# 1_Schematic_Antenna_Mini-Whip_SMD.net
KiCad netlist of a schematic drawn in EasyEDA
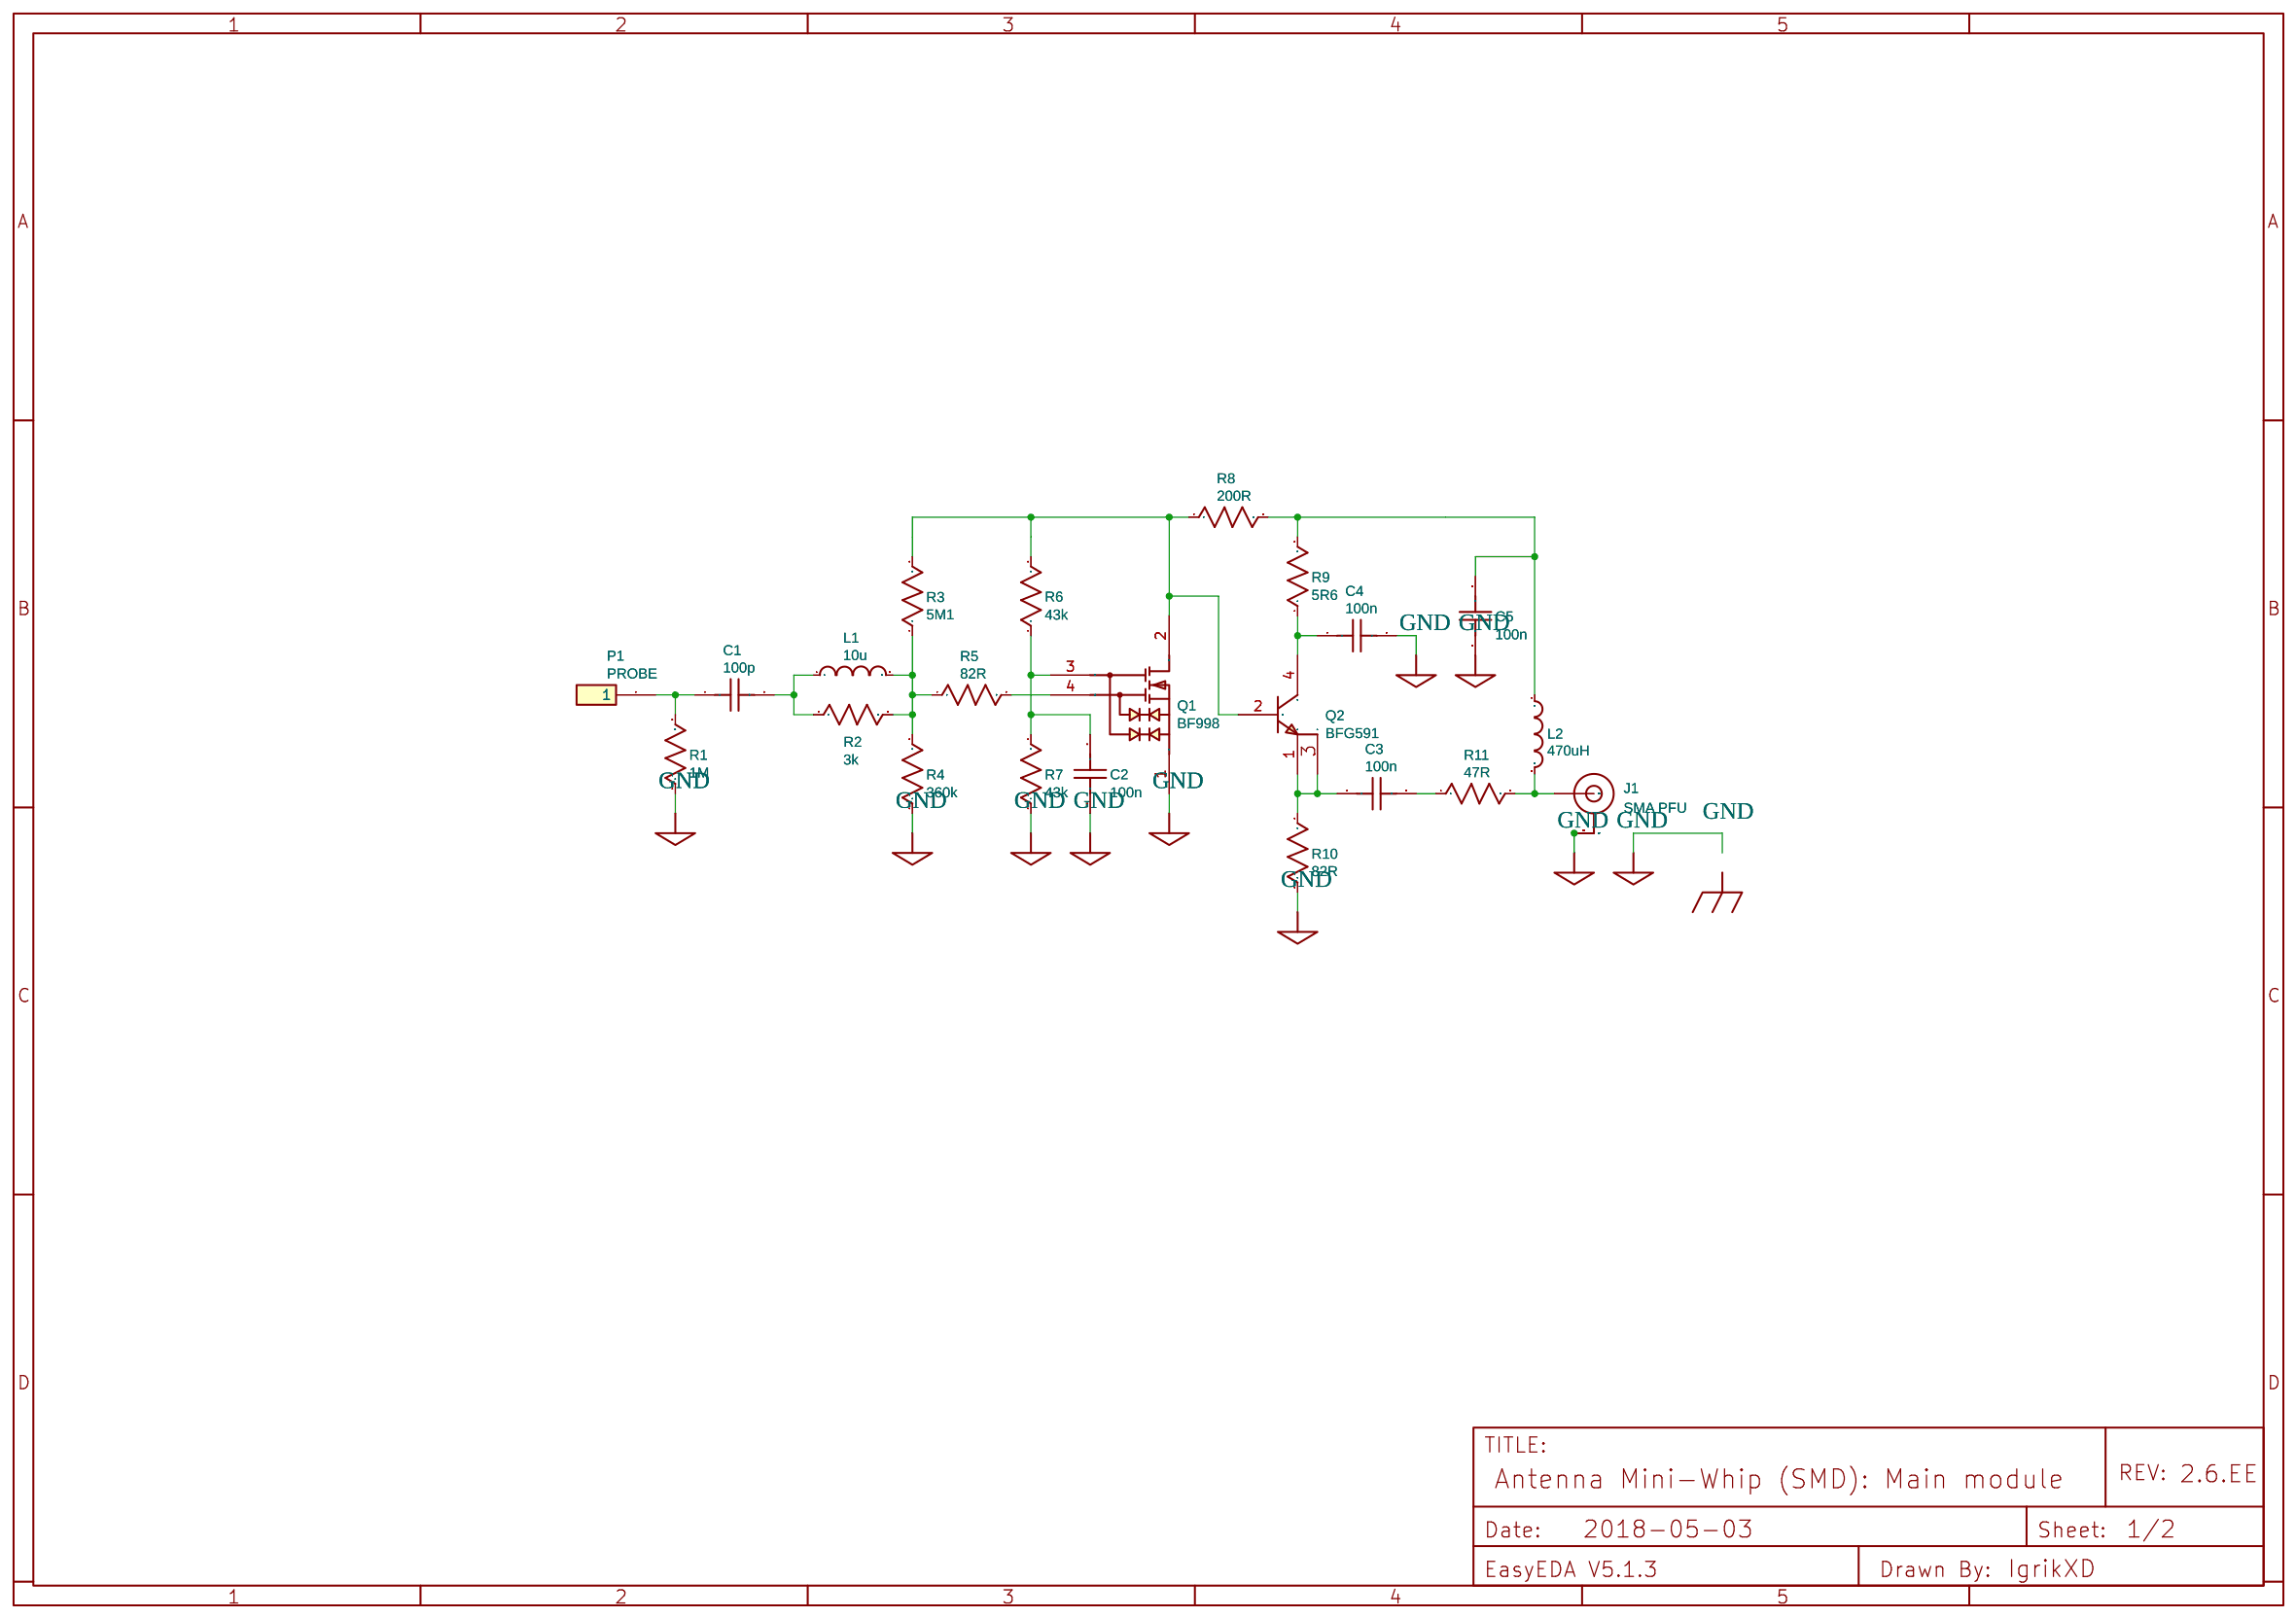
[diagram p0: Antenna Mini-Whip (SMD): Main module]
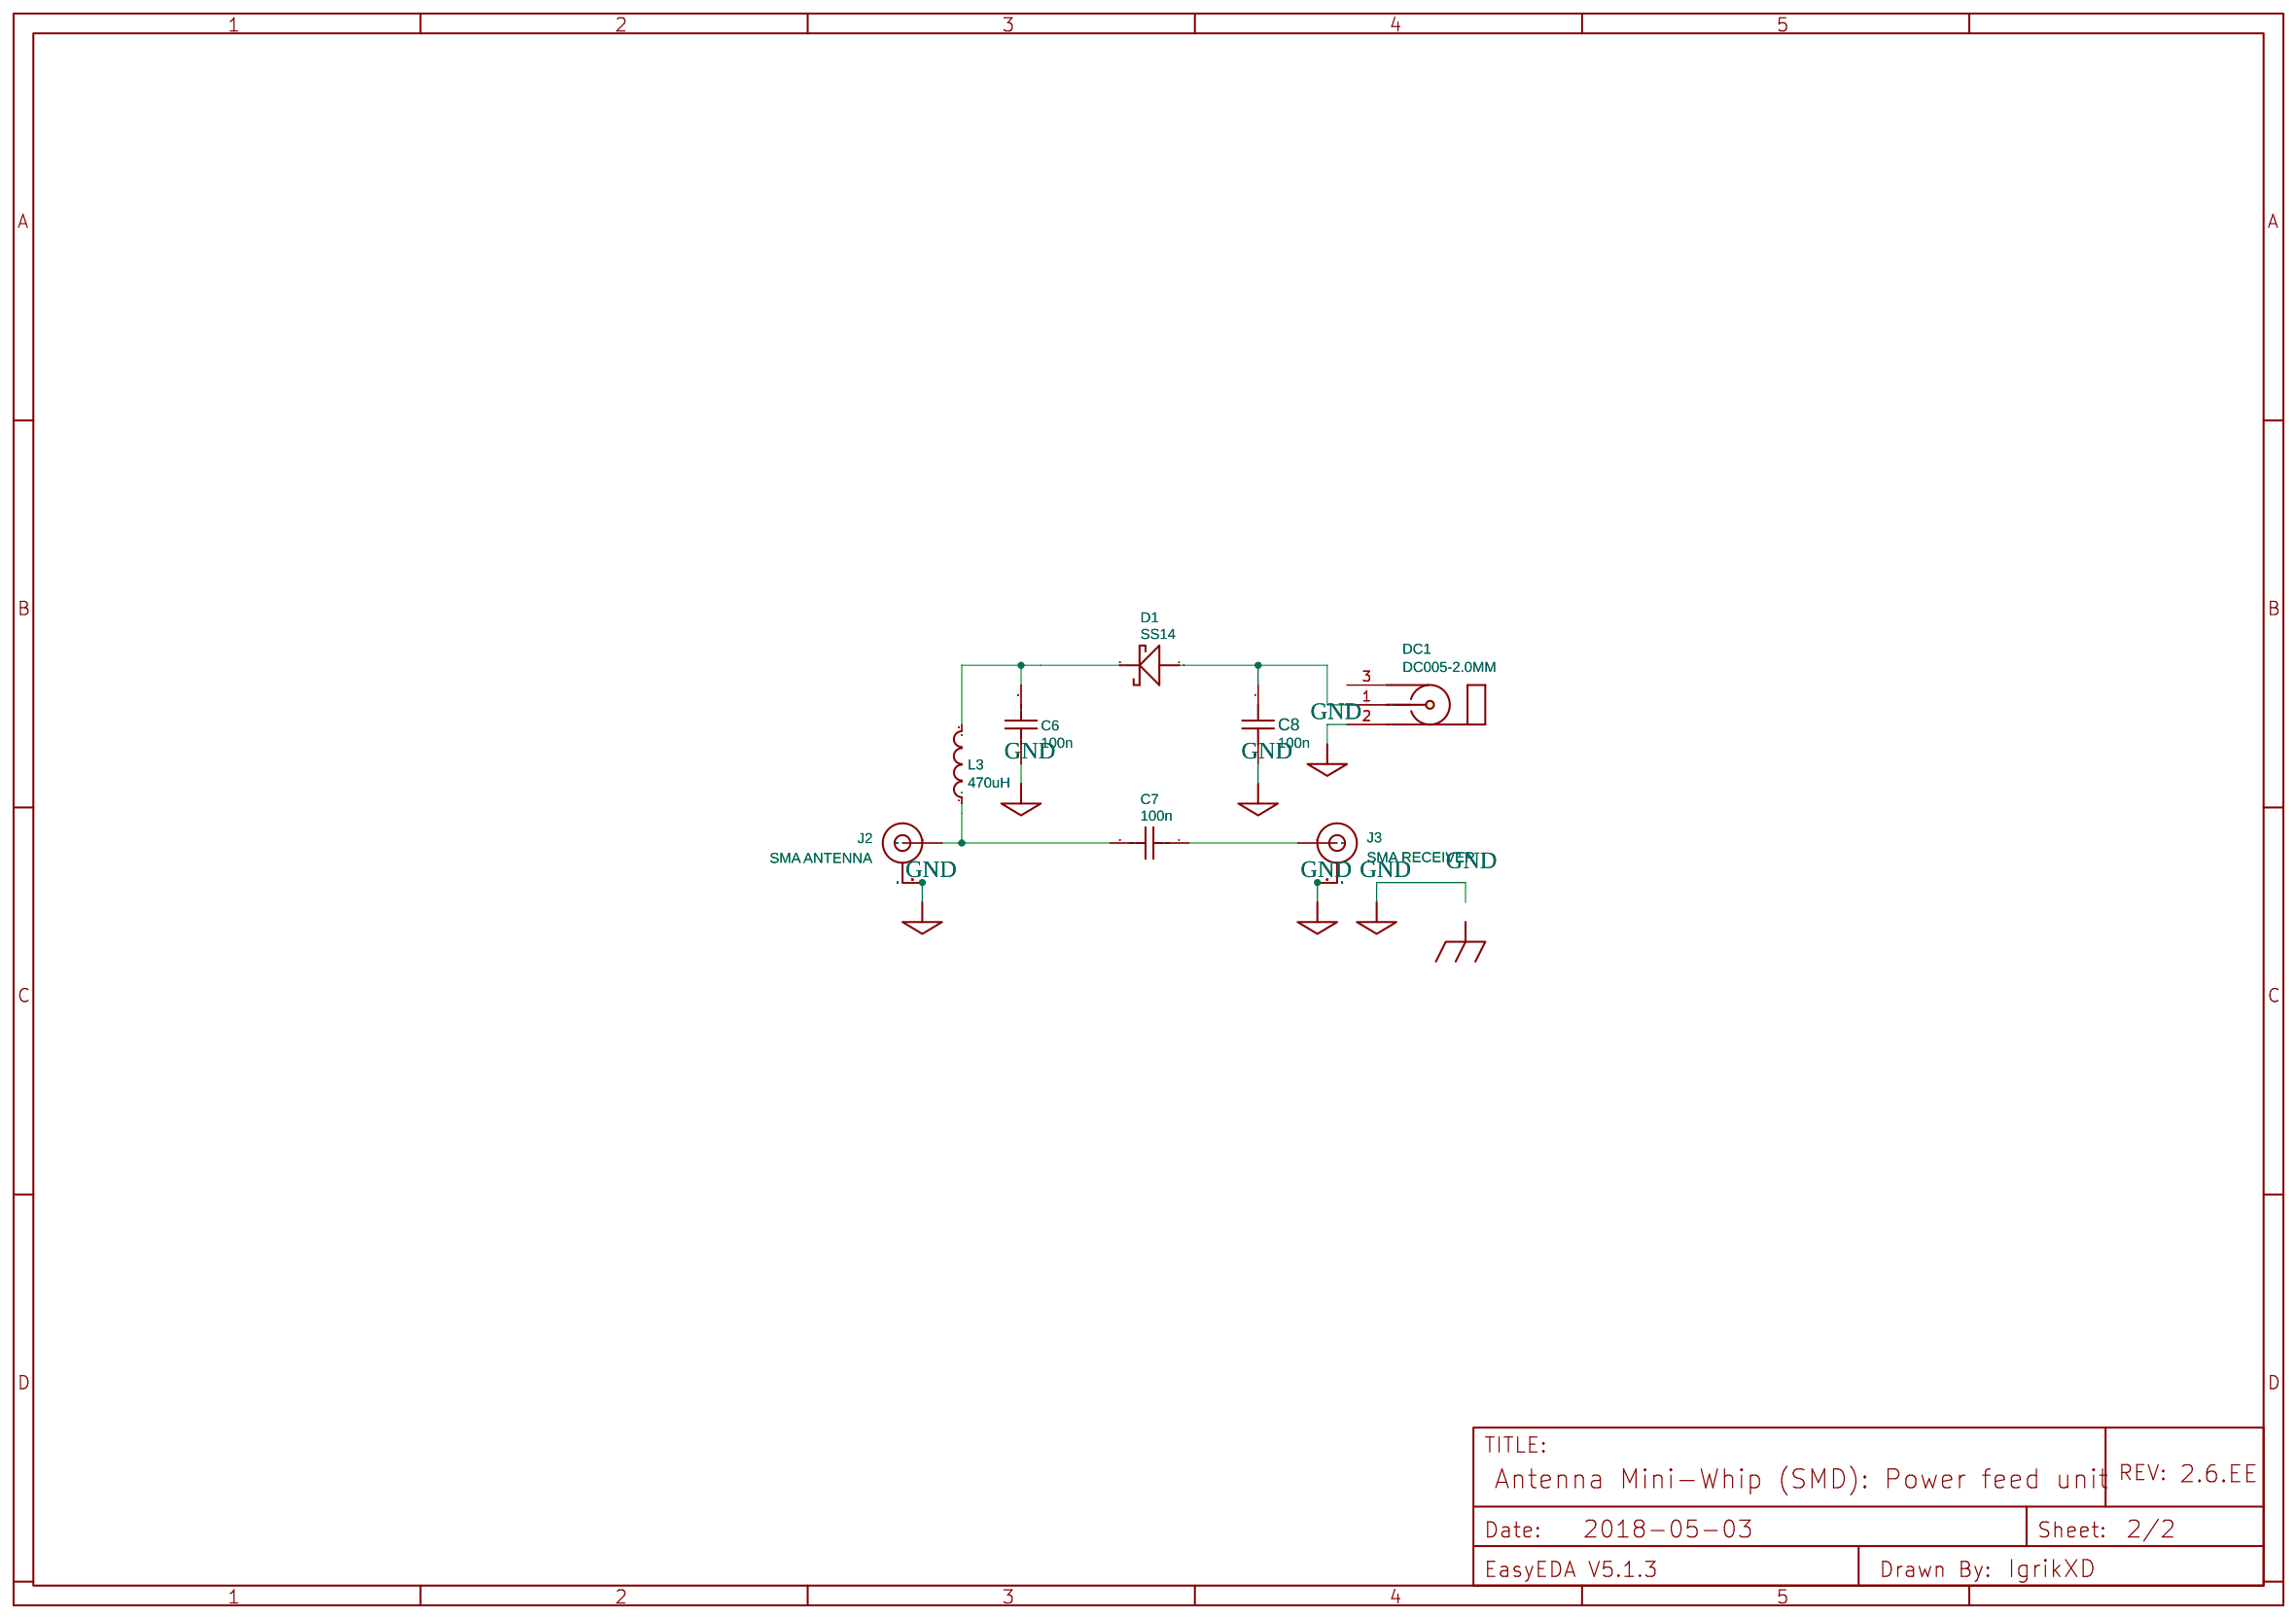
[diagram p1: Antenna Mini-Whip (SMD): Power feed unit]

(export (version "E")
  (design (tool "Eeschema 10.0.6"))
  (components
    (comp (ref "C1")
      (value "100p")
      (fields (field (name "BOM_Manufacturer Part") "CC0805JRNPOBBN101"))
      (libsource (lib "") (part "Capacitor_1"))
    )
    (comp (ref "C2")
      (value "100n")
      (fields (field (name "BOM_Manufacturer Part") "08055C104JAT2A"))
      (libsource (lib "") (part "Capacitor"))
    )
    (comp (ref "C3")
      (value "100n")
      (fields (field (name "BOM_Manufacturer Part") "08055C104JAT2A"))
      (libsource (lib "") (part "Capacitor_1"))
    )
    (comp (ref "C4")
      (value "100n")
      (fields (field (name "BOM_Manufacturer Part") "08055C104JAT2A"))
      (libsource (lib "") (part "Capacitor_1"))
    )
    (comp (ref "C5")
      (value "100n")
      (fields (field (name "BOM_Manufacturer Part") "08055C104JAT2A"))
      (libsource (lib "") (part "Capacitor"))
    )
    (comp (ref "J1")
      (value "SMA PFU")
      (fields (field (name "BOM_Manufacturer Part") "CON-SMA-EDGE-S"))
      (libsource (lib "") (part "Unknown_800_395"))
    )
    (comp (ref "L1")
      (value "10u")
      (fields (field (name "BOM_Manufacturer Part") "MLF2012E100JT000"))
      (libsource (lib "") (part "Inductor"))
    )
    (comp (ref "L2")
      (value "470uH")
      (fields (field (name "BOM_Manufacturer Part") "SM7850-471MT"))
      (libsource (lib "") (part "Unknown_770_365"))
    )
    (comp (ref "P1")
      (value "PROBE")
      (fields (field (name "BOM_Manufacturer Part") "Header-Male-2.54_1x1"))
      (libsource (lib "") (part "Unknown_310_345"))
    )
    (comp (ref "Q1")
      (value "BF998")
      (fields (field (name "BOM_Manufacturer Part") "BF998E6327HTSA1"))
      (libsource (lib "") (part "Unknown_565_355"))
    )
    (comp (ref "Q2")
      (value "BFG591")
      (fields (field (name "BOM_Manufacturer Part") "BFG591,115"))
      (libsource (lib "") (part "Unknown_640_355"))
    )
    (comp (ref "R1")
      (value "1M")
      (fields (field (name "BOM_Manufacturer Part") "RC0805FR-071ML"))
      (libsource (lib "") (part "Resistor"))
    )
    (comp (ref "R2")
      (value "3k")
      (fields (field (name "BOM_Manufacturer Part") "RC0805FR-073KL"))
      (libsource (lib "") (part "Resistor_1"))
    )
    (comp (ref "R3")
      (value "5M1")
      (fields (field (name "BOM_Manufacturer Part") "RC0805FR-075M1L"))
      (libsource (lib "") (part "Resistor"))
    )
    (comp (ref "R4")
      (value "360k")
      (fields (field (name "BOM_Manufacturer Part") "RC0805FR-07360KL"))
      (libsource (lib "") (part "Resistor"))
    )
    (comp (ref "R5")
      (value "82R")
      (fields (field (name "BOM_Manufacturer Part") "RTT0582R0FTP"))
      (libsource (lib "") (part "Resistor_1"))
    )
    (comp (ref "R6")
      (value "43k")
      (fields (field (name "BOM_Manufacturer Part") "RTT054302FTP"))
      (libsource (lib "") (part "Resistor"))
    )
    (comp (ref "R7")
      (value "43k")
      (fields (field (name "BOM_Manufacturer Part") "RTT054302FTP"))
      (libsource (lib "") (part "Resistor"))
    )
    (comp (ref "R8")
      (value "200R")
      (fields (field (name "BOM_Manufacturer Part") "RTT052000FTP"))
      (libsource (lib "") (part "Resistor_1"))
    )
    (comp (ref "R9")
      (value "5R6")
      (fields (field (name "BOM_Manufacturer Part") "CR0805F85R60G"))
      (libsource (lib "") (part "Resistor"))
    )
    (comp (ref "R10")
      (value "82R")
      (fields (field (name "BOM_Manufacturer Part") "RTT0582R0FTP"))
      (libsource (lib "") (part "Resistor"))
    )
    (comp (ref "R11")
      (value "47R")
      (fields (field (name "BOM_Manufacturer Part") "RTT0547R0FTP"))
      (libsource (lib "") (part "Resistor_1"))
    )
    (comp (ref "C6")
      (value "100n")
      (fields (field (name "BOM_Manufacturer Part") "08055C104JAT2A"))
      (libsource (lib "") (part "Capacitor"))
    )
    (comp (ref "C7")
      (value "100n")
      (fields (field (name "BOM_Manufacturer Part") "08055C104JAT2A"))
      (libsource (lib "") (part "Capacitor_1"))
    )
    (comp (ref "C8")
      (value "100n")
      (fields (field (name "BOM_Manufacturer Part") "08055C104JAT2A"))
      (libsource (lib "") (part "Capacitor"))
    )
    (comp (ref "D1")
      (value "SS14")
      (fields (field (name "BOM_Manufacturer Part") "SS14D"))
      (libsource (lib "") (part "Unknown_575_330"))
    )
    (comp (ref "DC1")
      (value "DC005-2.0MM")
      (fields (field (name "BOM_Manufacturer Part") "DC-005 5.5-2.0MM"))
      (libsource (lib "") (part "Unknown_705_350"))
    )
    (comp (ref "J2")
      (value "SMA ANTENNA")
      (fields (field (name "BOM_Manufacturer Part") "CON-SMA-EDGE-S"))
      (libsource (lib "") (part "Unknown_450_420"))
    )
    (comp (ref "J3")
      (value "SMA RECEIVER")
      (fields (field (name "BOM_Manufacturer Part") "CON-SMA-EDGE-S"))
      (libsource (lib "") (part "Unknown_670_420"))
    )
    (comp (ref "L3")
      (value "470uH")
      (fields (field (name "BOM_Manufacturer Part") "SM7850-471MT"))
      (libsource (lib "") (part "Unknown_480_380"))
    )
  )
  (nets
    (net (code "1") (name "GND") (class "Default")
      (node (ref "C2") (pin "1") (pinfunction "1_1") (pintype "unspecified"))
      (node (ref "C4") (pin "2") (pinfunction "2_2") (pintype "unspecified"))
      (node (ref "C5") (pin "1") (pinfunction "1_1") (pintype "unspecified"))
      (node (ref "C6") (pin "1") (pinfunction "1_1") (pintype "unspecified"))
      (node (ref "C8") (pin "1") (pinfunction "1_1") (pintype "unspecified"))
      (node (ref "DC1") (pin "2") (pinfunction "2_2") (pintype "input"))
      (node (ref "J1") (pin "GND@0") (pinfunction "GND_GND@0") (pintype "unspecified"))
      (node (ref "J1") (pin "GND@1") (pinfunction "GND_GND@1") (pintype "unspecified"))
      (node (ref "J1") (pin "GND@2") (pinfunction "GND_GND@2") (pintype "unspecified"))
      (node (ref "J1") (pin "GND@3") (pinfunction "GND_GND@3") (pintype "unspecified"))
      (node (ref "J2") (pin "GND@0") (pinfunction "GND_GND@0") (pintype "unspecified"))
      (node (ref "J2") (pin "GND@1") (pinfunction "GND_GND@1") (pintype "unspecified"))
      (node (ref "J2") (pin "GND@2") (pinfunction "GND_GND@2") (pintype "unspecified"))
      (node (ref "J2") (pin "GND@3") (pinfunction "GND_GND@3") (pintype "unspecified"))
      (node (ref "J3") (pin "GND@0") (pinfunction "GND_GND@0") (pintype "unspecified"))
      (node (ref "J3") (pin "GND@1") (pinfunction "GND_GND@1") (pintype "unspecified"))
      (node (ref "J3") (pin "GND@2") (pinfunction "GND_GND@2") (pintype "unspecified"))
      (node (ref "J3") (pin "GND@3") (pinfunction "GND_GND@3") (pintype "unspecified"))
      (node (ref "Q1") (pin "1") (pinfunction "S_1") (pintype "unspecified"))
      (node (ref "R1") (pin "1") (pinfunction "1_1") (pintype "unspecified"))
      (node (ref "R10") (pin "1") (pinfunction "1_1") (pintype "unspecified"))
      (node (ref "R4") (pin "1") (pinfunction "1_1") (pintype "unspecified"))
      (node (ref "R7") (pin "1") (pinfunction "1_1") (pintype "unspecified"))
    )
    (net (code "2") (name "Net-(C1-Pad1)") (class "Default")
      (node (ref "C1") (pin "1") (pinfunction "1_1") (pintype "unspecified"))
      (node (ref "P1") (pin "1") (pinfunction "1_1") (pintype "input"))
      (node (ref "R1") (pin "2") (pinfunction "2_2") (pintype "unspecified"))
    )
    (net (code "3") (name "Net-(C1-Pad2)") (class "Default")
      (node (ref "C1") (pin "2") (pinfunction "2_2") (pintype "unspecified"))
      (node (ref "L1") (pin "1") (pinfunction "1_1") (pintype "unspecified"))
      (node (ref "R2") (pin "1") (pinfunction "1_1") (pintype "unspecified"))
    )
    (net (code "4") (name "Net-(C3-Pad1)") (class "Default")
      (node (ref "C3") (pin "1") (pinfunction "1_1") (pintype "unspecified"))
      (node (ref "Q2") (pin "1") (pinfunction "E_1") (pintype "unspecified"))
      (node (ref "Q2") (pin "3") (pinfunction "E_3") (pintype "unspecified"))
      (node (ref "R10") (pin "2") (pinfunction "2_2") (pintype "unspecified"))
    )
    (net (code "5") (name "Net-(C3-Pad2)") (class "Default")
      (node (ref "C3") (pin "2") (pinfunction "2_2") (pintype "unspecified"))
      (node (ref "R11") (pin "1") (pinfunction "1_1") (pintype "unspecified"))
    )
    (net (code "6") (name "Net-(C5-Pad2)") (class "Default")
      (node (ref "C5") (pin "2") (pinfunction "2_2") (pintype "unspecified"))
      (node (ref "L2") (pin "1") (pinfunction "1_1") (pintype "unspecified"))
      (node (ref "R8") (pin "2") (pinfunction "2_2") (pintype "unspecified"))
      (node (ref "R9") (pin "2") (pinfunction "2_2") (pintype "unspecified"))
    )
    (net (code "7") (name "Net-(D1-A)") (class "Default")
      (node (ref "C8") (pin "2") (pinfunction "2_2") (pintype "unspecified"))
      (node (ref "D1") (pin "1") (pinfunction "A_1") (pintype "unspecified"))
      (node (ref "DC1") (pin "1") (pinfunction "VCC_1") (pintype "input"))
    )
    (net (code "8") (name "Net-(D1-C)") (class "Default")
      (node (ref "C6") (pin "2") (pinfunction "2_2") (pintype "unspecified"))
      (node (ref "D1") (pin "2") (pinfunction "C_2") (pintype "unspecified"))
      (node (ref "L3") (pin "2") (pinfunction "2_2") (pintype "unspecified"))
    )
    (net (code "9") (name "Net-(J1-SIGNAL)") (class "Default")
      (node (ref "J1") (pin "SIG") (pinfunction "SIGNAL_SIG") (pintype "unspecified"))
      (node (ref "L2") (pin "2") (pinfunction "2_2") (pintype "unspecified"))
      (node (ref "R11") (pin "2") (pinfunction "2_2") (pintype "unspecified"))
    )
    (net (code "10") (name "Net-(J2-SIGNAL)") (class "Default")
      (node (ref "C7") (pin "2") (pinfunction "2_2") (pintype "unspecified"))
      (node (ref "J2") (pin "SIG") (pinfunction "SIGNAL_SIG") (pintype "unspecified"))
      (node (ref "L3") (pin "1") (pinfunction "1_1") (pintype "unspecified"))
    )
    (net (code "11") (name "Net-(J3-SIGNAL)") (class "Default")
      (node (ref "C7") (pin "1") (pinfunction "1_1") (pintype "unspecified"))
      (node (ref "J3") (pin "SIG") (pinfunction "SIGNAL_SIG") (pintype "unspecified"))
    )
    (net (code "12") (name "Net-(L1-Pad2)") (class "Default")
      (node (ref "L1") (pin "2") (pinfunction "2_2") (pintype "unspecified"))
      (node (ref "R2") (pin "2") (pinfunction "2_2") (pintype "unspecified"))
      (node (ref "R3") (pin "1") (pinfunction "1_1") (pintype "unspecified"))
      (node (ref "R4") (pin "2") (pinfunction "2_2") (pintype "unspecified"))
      (node (ref "R5") (pin "1") (pinfunction "1_1") (pintype "unspecified"))
    )
    (net (code "13") (name "Net-(Q1-D)") (class "Default")
      (node (ref "Q1") (pin "2") (pinfunction "D_2") (pintype "unspecified"))
      (node (ref "Q2") (pin "2") (pinfunction "B_2") (pintype "unspecified"))
      (node (ref "R3") (pin "2") (pinfunction "2_2") (pintype "unspecified"))
      (node (ref "R6") (pin "2") (pinfunction "2_2") (pintype "unspecified"))
      (node (ref "R8") (pin "1") (pinfunction "1_1") (pintype "unspecified"))
    )
    (net (code "14") (name "Net-(Q1-G1)") (class "Default")
      (node (ref "Q1") (pin "4") (pinfunction "G1_4") (pintype "unspecified"))
      (node (ref "R5") (pin "2") (pinfunction "2_2") (pintype "unspecified"))
    )
    (net (code "15") (name "Net-(Q1-G2)") (class "Default")
      (node (ref "C2") (pin "2") (pinfunction "2_2") (pintype "unspecified"))
      (node (ref "Q1") (pin "3") (pinfunction "G2_3") (pintype "unspecified"))
      (node (ref "R6") (pin "1") (pinfunction "1_1") (pintype "unspecified"))
      (node (ref "R7") (pin "2") (pinfunction "2_2") (pintype "unspecified"))
    )
    (net (code "16") (name "Net-(Q2-C)") (class "Default")
      (node (ref "C4") (pin "1") (pinfunction "1_1") (pintype "unspecified"))
      (node (ref "Q2") (pin "4") (pinfunction "C_4") (pintype "unspecified"))
      (node (ref "R9") (pin "1") (pinfunction "1_1") (pintype "unspecified"))
    )
    (net (code "17") (name "unconnected-(DC1-Pad3)") (class "Default")
      (node (ref "DC1") (pin "3") (pinfunction "3_3") (pintype "input"))
    )
  )
)
